# PolyPiezoProgrammer.net
KiCad netlist of a schematic drawn in EAGLE
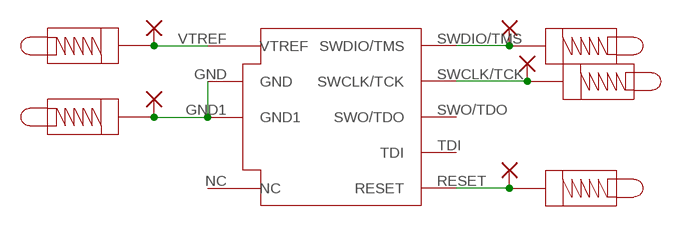
[diagram p0: schematic, sheet 1]

(export (version "E")
  (design (tool "Eeschema 10.0.6"))
  (components
    (comp (ref "PAD1")
      (value "WIREPAD2,15/1,0")
      (footprint "eagle-import:2,15_1,0")
      (libsource (lib "eagle-import") (part "WIREPAD2,15/1,0"))
    )
    (comp (ref "PAD2")
      (value "WIREPAD2,15/1,0")
      (footprint "eagle-import:2,15_1,0")
      (libsource (lib "eagle-import") (part "WIREPAD2,15/1,0"))
    )
    (comp (ref "PAD3")
      (value "WIREPAD2,15/1,0")
      (footprint "eagle-import:2,15_1,0")
      (libsource (lib "eagle-import") (part "WIREPAD2,15/1,0"))
    )
    (comp (ref "PAD4")
      (value "WIREPAD2,15/1,0")
      (footprint "eagle-import:2,15_1,0")
      (libsource (lib "eagle-import") (part "WIREPAD2,15/1,0"))
    )
    (comp (ref "PAD5")
      (value "WIREPAD2,15/1,0")
      (footprint "eagle-import:2,15_1,0")
      (libsource (lib "eagle-import") (part "WIREPAD2,15/1,0"))
    )
    (comp (ref "U$1")
      (value "0930-0-15-20-75-14-11-0")
      (footprint "eagle-import:0930-0-15-20-75-14-11-0")
      (libsource (lib "eagle-import") (part "0930-0-15-20-75-14-11-0"))
    )
    (comp (ref "U$2")
      (value "0930-0-15-20-75-14-11-0")
      (footprint "eagle-import:0930-0-15-20-75-14-11-0")
      (libsource (lib "eagle-import") (part "0930-0-15-20-75-14-11-0"))
    )
    (comp (ref "U$3")
      (value "0930-0-15-20-75-14-11-0")
      (footprint "eagle-import:0930-0-15-20-75-14-11-0")
      (libsource (lib "eagle-import") (part "0930-0-15-20-75-14-11-0"))
    )
    (comp (ref "U$4")
      (value "0930-0-15-20-75-14-11-0")
      (footprint "eagle-import:0930-0-15-20-75-14-11-0")
      (libsource (lib "eagle-import") (part "0930-0-15-20-75-14-11-0"))
    )
    (comp (ref "U$5")
      (value "0930-0-15-20-75-14-11-0")
      (footprint "eagle-import:0930-0-15-20-75-14-11-0")
      (libsource (lib "eagle-import") (part "0930-0-15-20-75-14-11-0"))
    )
    (comp (ref "U$6")
      (value "JLINK_IF")
      (footprint "eagle-import:JLINK_IF")
      (libsource (lib "eagle-import") (part "JLINK_IF"))
    )
  )
  (nets
    (net (code "1") (name "Net-(PAD1-P)") (class "Default")
      (node (ref "PAD1") (pin "1") (pinfunction "P_1") (pintype "passive"))
      (node (ref "U$2") (pin "P$1") (pinfunction "P$1_P$1") (pintype "bidirectional"))
      (node (ref "U$6") (pin "GND") (pinfunction "GND_GND") (pintype "bidirectional"))
      (node (ref "U$6") (pin "GND1") (pinfunction "GND1_GND1") (pintype "bidirectional"))
    )
    (net (code "2") (name "Net-(PAD2-P)") (class "Default")
      (node (ref "PAD2") (pin "1") (pinfunction "P_1") (pintype "passive"))
      (node (ref "U$1") (pin "P$1") (pinfunction "P$1_P$1") (pintype "bidirectional"))
      (node (ref "U$6") (pin "VTREF") (pinfunction "VTREF_VTREF") (pintype "bidirectional"))
    )
    (net (code "3") (name "Net-(PAD3-P)") (class "Default")
      (node (ref "PAD3") (pin "1") (pinfunction "P_1") (pintype "passive"))
      (node (ref "U$5") (pin "P$1") (pinfunction "P$1_P$1") (pintype "bidirectional"))
      (node (ref "U$6") (pin "RESET") (pinfunction "RESET_RESET") (pintype "bidirectional"))
    )
    (net (code "4") (name "Net-(PAD4-P)") (class "Default")
      (node (ref "PAD4") (pin "1") (pinfunction "P_1") (pintype "passive"))
      (node (ref "U$4") (pin "P$1") (pinfunction "P$1_P$1") (pintype "bidirectional"))
      (node (ref "U$6") (pin "SWCLK/TCK") (pinfunction "SWCLK/TCK_SWCLK/TCK") (pintype "bidirectional"))
    )
    (net (code "5") (name "Net-(PAD5-P)") (class "Default")
      (node (ref "PAD5") (pin "1") (pinfunction "P_1") (pintype "passive"))
      (node (ref "U$3") (pin "P$1") (pinfunction "P$1_P$1") (pintype "bidirectional"))
      (node (ref "U$6") (pin "SWDIO/TMS") (pinfunction "SWDIO/TMS_SWDIO/TMS") (pintype "bidirectional"))
    )
    (net (code "6") (name "unconnected-(U$6-PadNC)") (class "Default")
      (node (ref "U$6") (pin "NC") (pinfunction "NC_NC") (pintype "bidirectional"))
    )
    (net (code "7") (name "unconnected-(U$6-PadSWO{slash}TDO)") (class "Default")
      (node (ref "U$6") (pin "SWO/TDO") (pinfunction "SWO/TDO_SWO/TDO") (pintype "bidirectional"))
    )
    (net (code "8") (name "unconnected-(U$6-PadTDI)") (class "Default")
      (node (ref "U$6") (pin "TDI") (pinfunction "TDI_TDI") (pintype "bidirectional"))
    )
  )
)
